# voeding.net
KiCad netlist of a schematic drawn in Altium Designer
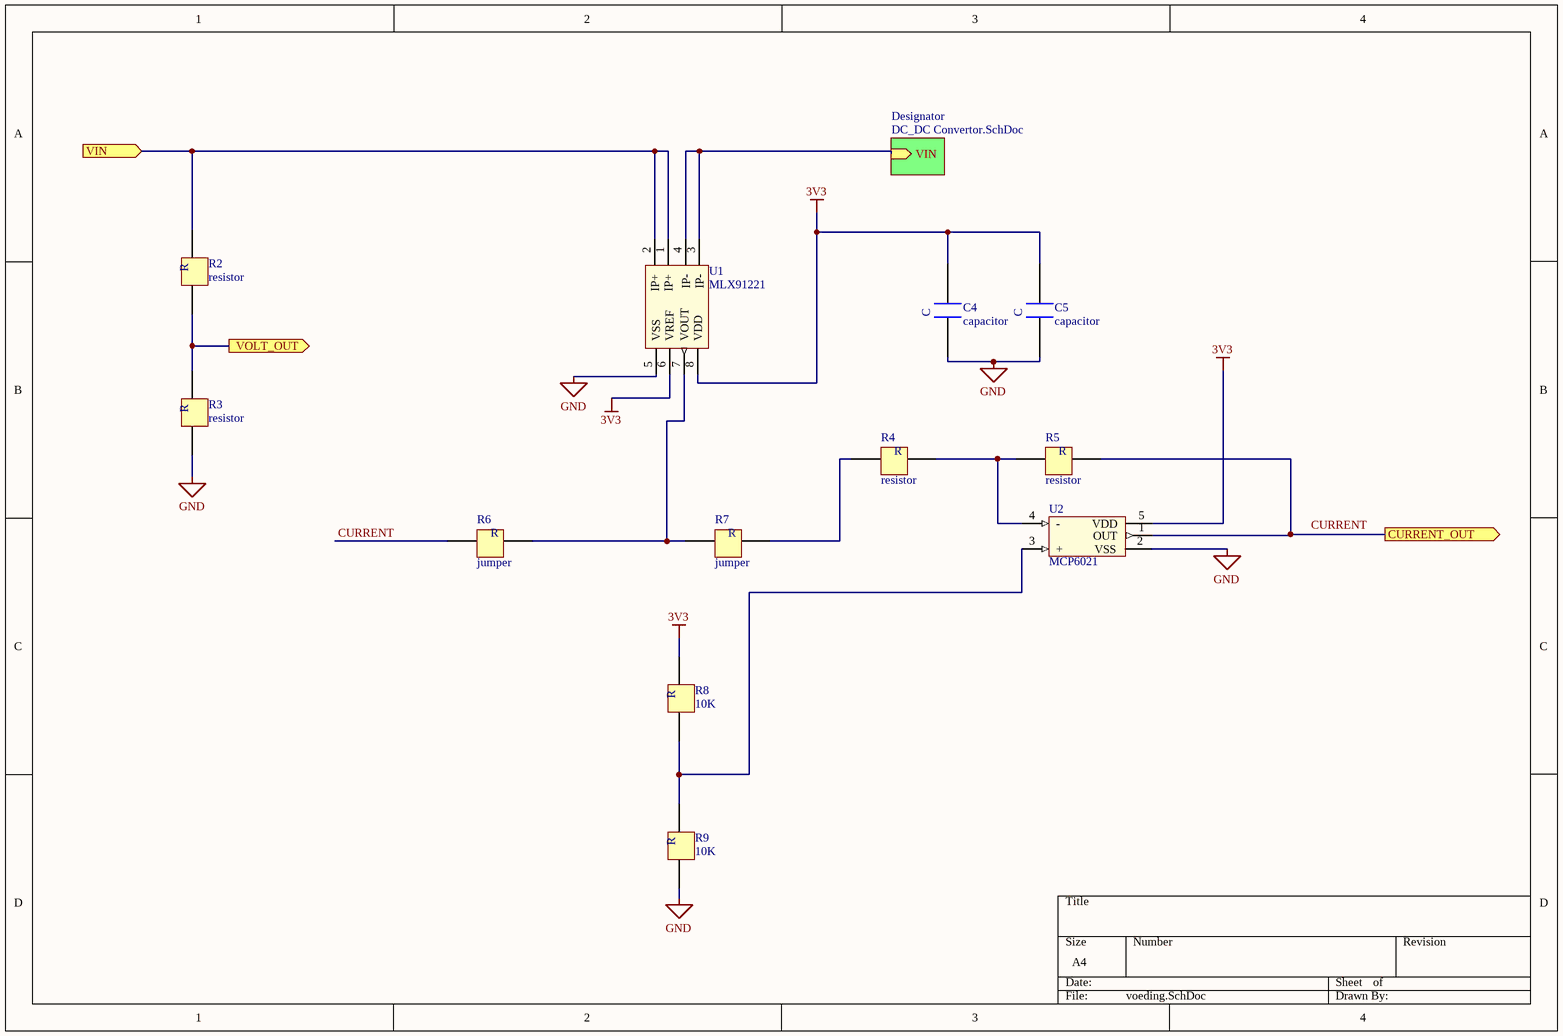
[diagram p0: voeding.SchDoc]

(export (version "E")
  (design (tool "Eeschema 10.0.6"))
  (components
    (comp (ref "C4") (value "capacitor") (footprint "0603") (libsource (lib "pasives") (part "capacitor")))
    (comp (ref "C5") (value "capacitor") (footprint "0603") (libsource (lib "pasives") (part "capacitor")))
    (comp (ref "R2") (value "resistor") (footprint "0603") (libsource (lib "") (part "resistor_1")))
    (comp (ref "R3") (value "resistor") (footprint "0603") (libsource (lib "") (part "resistor_1")))
    (comp (ref "R4") (value "resistor") (footprint "0603") (libsource (lib "pasives") (part "resistor")))
    (comp (ref "R5") (value "resistor") (footprint "0603") (libsource (lib "pasives") (part "resistor")))
    (comp (ref "R6") (value "jumper") (footprint "0603") (libsource (lib "pasives") (part "resistor")))
    (comp (ref "R7") (value "jumper") (footprint "0603") (libsource (lib "pasives") (part "resistor")))
    (comp (ref "R8") (value "10K") (footprint "CAPC1005X04L") (libsource (lib "") (part "resistor_1")))
    (comp (ref "R9") (value "10K") (footprint "CAPC1005X04L") (libsource (lib "") (part "resistor_1")))
    (comp (ref "U1")
      (value "MLX91221")
      (footprint "SOIC8")
      (libsource (lib "halfgelijders") (part "MLX91221"))
    )
    (comp (ref "U2")
      (value "MCP6021")
      (footprint "AP2112 sot25")
      (libsource (lib "halfgelijders") (part "MCP6021"))
    )
  )
  (nets
    (net (code "1") (name "/CURRENT") (class "Default")
      (node (ref "R6") (pin "2") (pinfunction "2_2") (pintype "passive"))
    )
    (net (code "2") (name "/CURRENT_OUT") (class "Default")
      (node (ref "R5") (pin "1") (pinfunction "1_1") (pintype "passive"))
      (node (ref "U2") (pin "1") (pinfunction "OUT_1") (pintype "output"))
    )
    (net (code "3") (name "/VIN") (class "Default")
      (node (ref "R2") (pin "1") (pinfunction "1_1") (pintype "passive"))
      (node (ref "U1") (pin "1") (pinfunction "IP+_1") (pintype "power_in"))
      (node (ref "U1") (pin "2") (pinfunction "IP+_2") (pintype "power_in"))
    )
    (net (code "4") (name "/VIN_1") (class "Default")
      (node (ref "U1") (pin "3") (pinfunction "IP-_3") (pintype "power_in"))
      (node (ref "U1") (pin "4") (pinfunction "IP-_4") (pintype "power_in"))
    )
    (net (code "5") (name "/VOLT_OUT") (class "Default")
      (node (ref "R2") (pin "2") (pinfunction "2_2") (pintype "passive"))
      (node (ref "R3") (pin "1") (pinfunction "1_1") (pintype "passive"))
    )
    (net (code "6") (name "3V3") (class "Default")
      (node (ref "C4") (pin "1") (pinfunction "1_1") (pintype "passive"))
      (node (ref "C5") (pin "1") (pinfunction "1_1") (pintype "passive"))
      (node (ref "R8") (pin "1") (pinfunction "1_1") (pintype "passive"))
      (node (ref "U1") (pin "6") (pinfunction "VREF_6") (pintype "power_in"))
      (node (ref "U1") (pin "8") (pinfunction "VDD_8") (pintype "power_in"))
      (node (ref "U2") (pin "5") (pinfunction "VDD_5") (pintype "power_in"))
    )
    (net (code "7") (name "GND") (class "Default")
      (node (ref "C4") (pin "2") (pinfunction "2_2") (pintype "passive"))
      (node (ref "C5") (pin "2") (pinfunction "2_2") (pintype "passive"))
      (node (ref "R3") (pin "2") (pinfunction "2_2") (pintype "passive"))
      (node (ref "R9") (pin "2") (pinfunction "2_2") (pintype "passive"))
      (node (ref "U1") (pin "5") (pinfunction "VSS_5") (pintype "power_in"))
      (node (ref "U2") (pin "2") (pinfunction "VSS_2") (pintype "power_in"))
    )
    (net (code "8") (name "Net-(R4-Pad2)") (class "Default")
      (node (ref "R4") (pin "2") (pinfunction "2_2") (pintype "passive"))
      (node (ref "R7") (pin "1") (pinfunction "1_1") (pintype "passive"))
    )
    (net (code "9") (name "Net-(U1-VOUT)") (class "Default")
      (node (ref "R6") (pin "1") (pinfunction "1_1") (pintype "passive"))
      (node (ref "R7") (pin "2") (pinfunction "2_2") (pintype "passive"))
      (node (ref "U1") (pin "7") (pinfunction "VOUT_7") (pintype "output"))
    )
    (net (code "10") (name "Net-(U2-+)") (class "Default")
      (node (ref "R8") (pin "2") (pinfunction "2_2") (pintype "passive"))
      (node (ref "R9") (pin "1") (pinfunction "1_1") (pintype "passive"))
      (node (ref "U2") (pin "3") (pinfunction "+_3") (pintype "input"))
    )
    (net (code "11") (name "Net-(U2--)") (class "Default")
      (node (ref "R4") (pin "1") (pinfunction "1_1") (pintype "passive"))
      (node (ref "R5") (pin "2") (pinfunction "2_2") (pintype "passive"))
      (node (ref "U2") (pin "4") (pinfunction "-_4") (pintype "input"))
    )
  )
)
